# connectors.net
KiCad netlist of a schematic drawn in Altium Designer
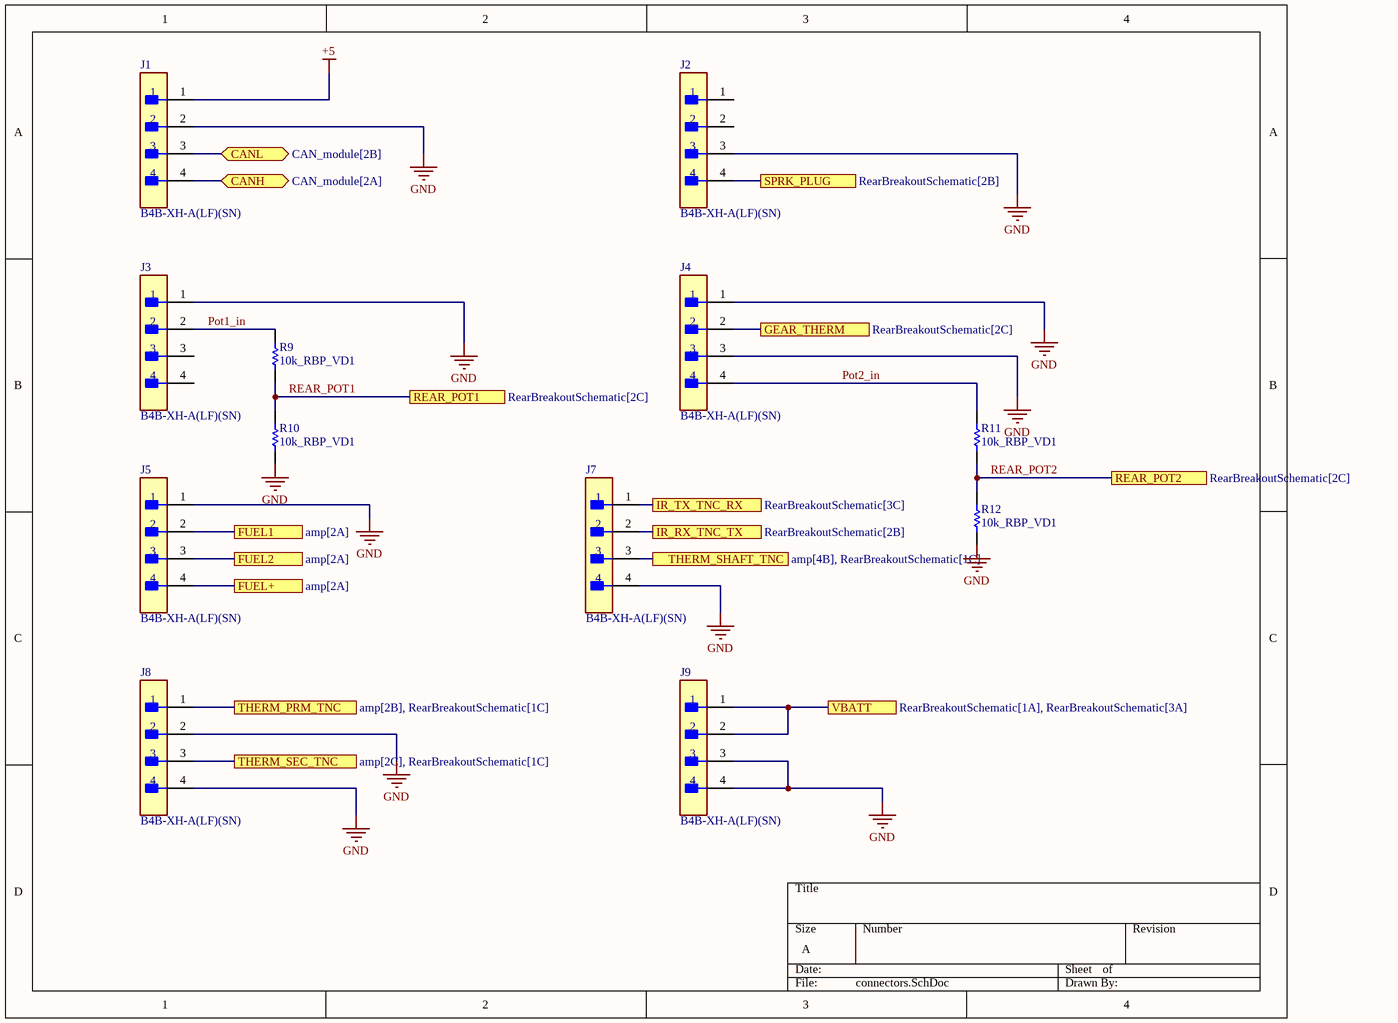
[diagram p0: connectors.SchDoc]

(export (version "E")
  (design (tool "Eeschema 10.0.6"))
  (components
    (comp (ref "J1")
      (value "B4B-XH-A(LF)(SN)")
      (footprint "FP-B4B-XH-A_LF_SN-MFG")
      (description "CONN HEADER VERT 4POS 2.5MM")
      (libsource (lib "Altium Content Vault") (part "299a8cea1bdcbc3624fe62c390fa72c"))
    )
    (comp (ref "J2")
      (value "B4B-XH-A(LF)(SN)")
      (footprint "FP-B4B-XH-A_LF_SN-MFG")
      (description "CONN HEADER VERT 4POS 2.5MM")
      (libsource (lib "Altium Content Vault") (part "299a8cea1bdcbc3624fe62c390fa72c"))
    )
    (comp (ref "J3")
      (value "B4B-XH-A(LF)(SN)")
      (footprint "FP-B4B-XH-A_LF_SN-MFG")
      (description "CONN HEADER VERT 4POS 2.5MM")
      (libsource (lib "Altium Content Vault") (part "299a8cea1bdcbc3624fe62c390fa72c"))
    )
    (comp (ref "J4")
      (value "B4B-XH-A(LF)(SN)")
      (footprint "FP-B4B-XH-A_LF_SN-MFG")
      (description "CONN HEADER VERT 4POS 2.5MM")
      (libsource (lib "Altium Content Vault") (part "299a8cea1bdcbc3624fe62c390fa72c"))
    )
    (comp (ref "J5")
      (value "B4B-XH-A(LF)(SN)")
      (footprint "FP-B4B-XH-A_LF_SN-MFG")
      (description "CONN HEADER VERT 4POS 2.5MM")
      (libsource (lib "Altium Content Vault") (part "299a8cea1bdcbc3624fe62c390fa72c"))
    )
    (comp (ref "J7")
      (value "B4B-XH-A(LF)(SN)")
      (footprint "FP-B4B-XH-A_LF_SN-MFG")
      (description "CONN HEADER VERT 4POS 2.5MM")
      (libsource (lib "Altium Content Vault") (part "299a8cea1bdcbc3624fe62c390fa72c"))
    )
    (comp (ref "J8")
      (value "B4B-XH-A(LF)(SN)")
      (footprint "FP-B4B-XH-A_LF_SN-MFG")
      (description "CONN HEADER VERT 4POS 2.5MM")
      (libsource (lib "Altium Content Vault") (part "299a8cea1bdcbc3624fe62c390fa72c"))
    )
    (comp (ref "J9")
      (value "B4B-XH-A(LF)(SN)")
      (footprint "FP-B4B-XH-A_LF_SN-MFG")
      (description "CONN HEADER VERT 4POS 2.5MM")
      (libsource (lib "Altium Content Vault") (part "299a8cea1bdcbc3624fe62c390fa72c"))
    )
    (comp (ref "R9")
      (value "10k_RBP_VD1")
      (footprint "RESC2013X60X40LL20T25")
      (fields (field (name "MANUFACTURER") "Panasonic") (field (name "PART NUMBER") "ERA6AEB7870V"))
      (libsource (lib "Altium Content Vault") (part "RES"))
    )
    (comp (ref "R10")
      (value "10k_RBP_VD1")
      (footprint "RESC2013X60X40LL20T25")
      (fields (field (name "MANUFACTURER") "Panasonic") (field (name "PART NUMBER") "ERA6AEB7870V"))
      (libsource (lib "Altium Content Vault") (part "RES"))
    )
    (comp (ref "R11")
      (value "10k_RBP_VD1")
      (footprint "RESC2013X60X40LL20T25")
      (fields (field (name "MANUFACTURER") "Panasonic") (field (name "PART NUMBER") "ERA6AEB7870V"))
      (libsource (lib "Altium Content Vault") (part "RES"))
    )
    (comp (ref "R12")
      (value "10k_RBP_VD1")
      (footprint "RESC2013X60X40LL20T25")
      (fields (field (name "MANUFACTURER") "Panasonic") (field (name "PART NUMBER") "ERA6AEB7870V"))
      (libsource (lib "Altium Content Vault") (part "RES"))
    )
  )
  (nets
    (net (code "1") (name "+5") (class "Default")
      (node (ref "J1") (pin "1") (pinfunction "1_1") (pintype "passive"))
    )
    (net (code "2") (name "/CANH") (class "Default")
      (node (ref "J1") (pin "4") (pinfunction "4_4") (pintype "passive"))
    )
    (net (code "3") (name "/CANL") (class "Default")
      (node (ref "J1") (pin "3") (pinfunction "3_3") (pintype "passive"))
    )
    (net (code "4") (name "/FUEL+") (class "Default")
      (node (ref "J5") (pin "4") (pinfunction "4_4") (pintype "passive"))
    )
    (net (code "5") (name "/FUEL1") (class "Default")
      (node (ref "J5") (pin "2") (pinfunction "2_2") (pintype "passive"))
    )
    (net (code "6") (name "/FUEL2") (class "Default")
      (node (ref "J5") (pin "3") (pinfunction "3_3") (pintype "passive"))
    )
    (net (code "7") (name "/GEAR_THERM") (class "Default")
      (node (ref "J4") (pin "2") (pinfunction "2_2") (pintype "passive"))
    )
    (net (code "8") (name "/IR_RX_TNC_TX") (class "Default")
      (node (ref "J7") (pin "2") (pinfunction "2_2") (pintype "passive"))
    )
    (net (code "9") (name "/IR_TX_TNC_RX") (class "Default")
      (node (ref "J7") (pin "1") (pinfunction "1_1") (pintype "passive"))
    )
    (net (code "10") (name "/Pot1_in") (class "Default")
      (node (ref "J3") (pin "2") (pinfunction "2_2") (pintype "passive"))
      (node (ref "R9") (pin "2") (pinfunction "2_2") (pintype "passive"))
    )
    (net (code "11") (name "/Pot2_in") (class "Default")
      (node (ref "J4") (pin "4") (pinfunction "4_4") (pintype "passive"))
      (node (ref "R11") (pin "2") (pinfunction "2_2") (pintype "passive"))
    )
    (net (code "12") (name "/REAR_POT1") (class "Default")
      (node (ref "R10") (pin "2") (pinfunction "2_2") (pintype "passive"))
      (node (ref "R9") (pin "1") (pinfunction "1_1") (pintype "passive"))
    )
    (net (code "13") (name "/REAR_POT2") (class "Default")
      (node (ref "R11") (pin "1") (pinfunction "1_1") (pintype "passive"))
      (node (ref "R12") (pin "2") (pinfunction "2_2") (pintype "passive"))
    )
    (net (code "14") (name "/SPRK_PLUG") (class "Default")
      (node (ref "J2") (pin "4") (pinfunction "4_4") (pintype "passive"))
    )
    (net (code "15") (name "/THERM_PRM_TNC") (class "Default")
      (node (ref "J8") (pin "1") (pinfunction "1_1") (pintype "passive"))
    )
    (net (code "16") (name "/THERM_SEC_TNC") (class "Default")
      (node (ref "J8") (pin "3") (pinfunction "3_3") (pintype "passive"))
    )
    (net (code "17") (name "/THERM_SHAFT_TNC") (class "Default")
      (node (ref "J7") (pin "3") (pinfunction "3_3") (pintype "passive"))
    )
    (net (code "18") (name "/VBATT") (class "Default")
      (node (ref "J9") (pin "1") (pinfunction "1_1") (pintype "passive"))
      (node (ref "J9") (pin "2") (pinfunction "2_2") (pintype "passive"))
    )
    (net (code "19") (name "GND") (class "Default")
      (node (ref "J1") (pin "2") (pinfunction "2_2") (pintype "passive"))
      (node (ref "J2") (pin "3") (pinfunction "3_3") (pintype "passive"))
      (node (ref "J3") (pin "1") (pinfunction "1_1") (pintype "passive"))
      (node (ref "J4") (pin "1") (pinfunction "1_1") (pintype "passive"))
      (node (ref "J4") (pin "3") (pinfunction "3_3") (pintype "passive"))
      (node (ref "J5") (pin "1") (pinfunction "1_1") (pintype "passive"))
      (node (ref "J7") (pin "4") (pinfunction "4_4") (pintype "passive"))
      (node (ref "J8") (pin "2") (pinfunction "2_2") (pintype "passive"))
      (node (ref "J8") (pin "4") (pinfunction "4_4") (pintype "passive"))
      (node (ref "J9") (pin "3") (pinfunction "3_3") (pintype "passive"))
      (node (ref "J9") (pin "4") (pinfunction "4_4") (pintype "passive"))
      (node (ref "R10") (pin "1") (pinfunction "1_1") (pintype "passive"))
      (node (ref "R12") (pin "1") (pinfunction "1_1") (pintype "passive"))
    )
    (net (code "20") (name "unconnected-(J2-Pad1)") (class "Default")
      (node (ref "J2") (pin "1") (pinfunction "1_1") (pintype "passive"))
    )
    (net (code "21") (name "unconnected-(J2-Pad2)") (class "Default")
      (node (ref "J2") (pin "2") (pinfunction "2_2") (pintype "passive"))
    )
    (net (code "22") (name "unconnected-(J3-Pad3)") (class "Default")
      (node (ref "J3") (pin "3") (pinfunction "3_3") (pintype "passive"))
    )
    (net (code "23") (name "unconnected-(J3-Pad4)") (class "Default")
      (node (ref "J3") (pin "4") (pinfunction "4_4") (pintype "passive"))
    )
  )
)
